# Dramco_UNO.net
KiCad netlist of a schematic drawn in EAGLE
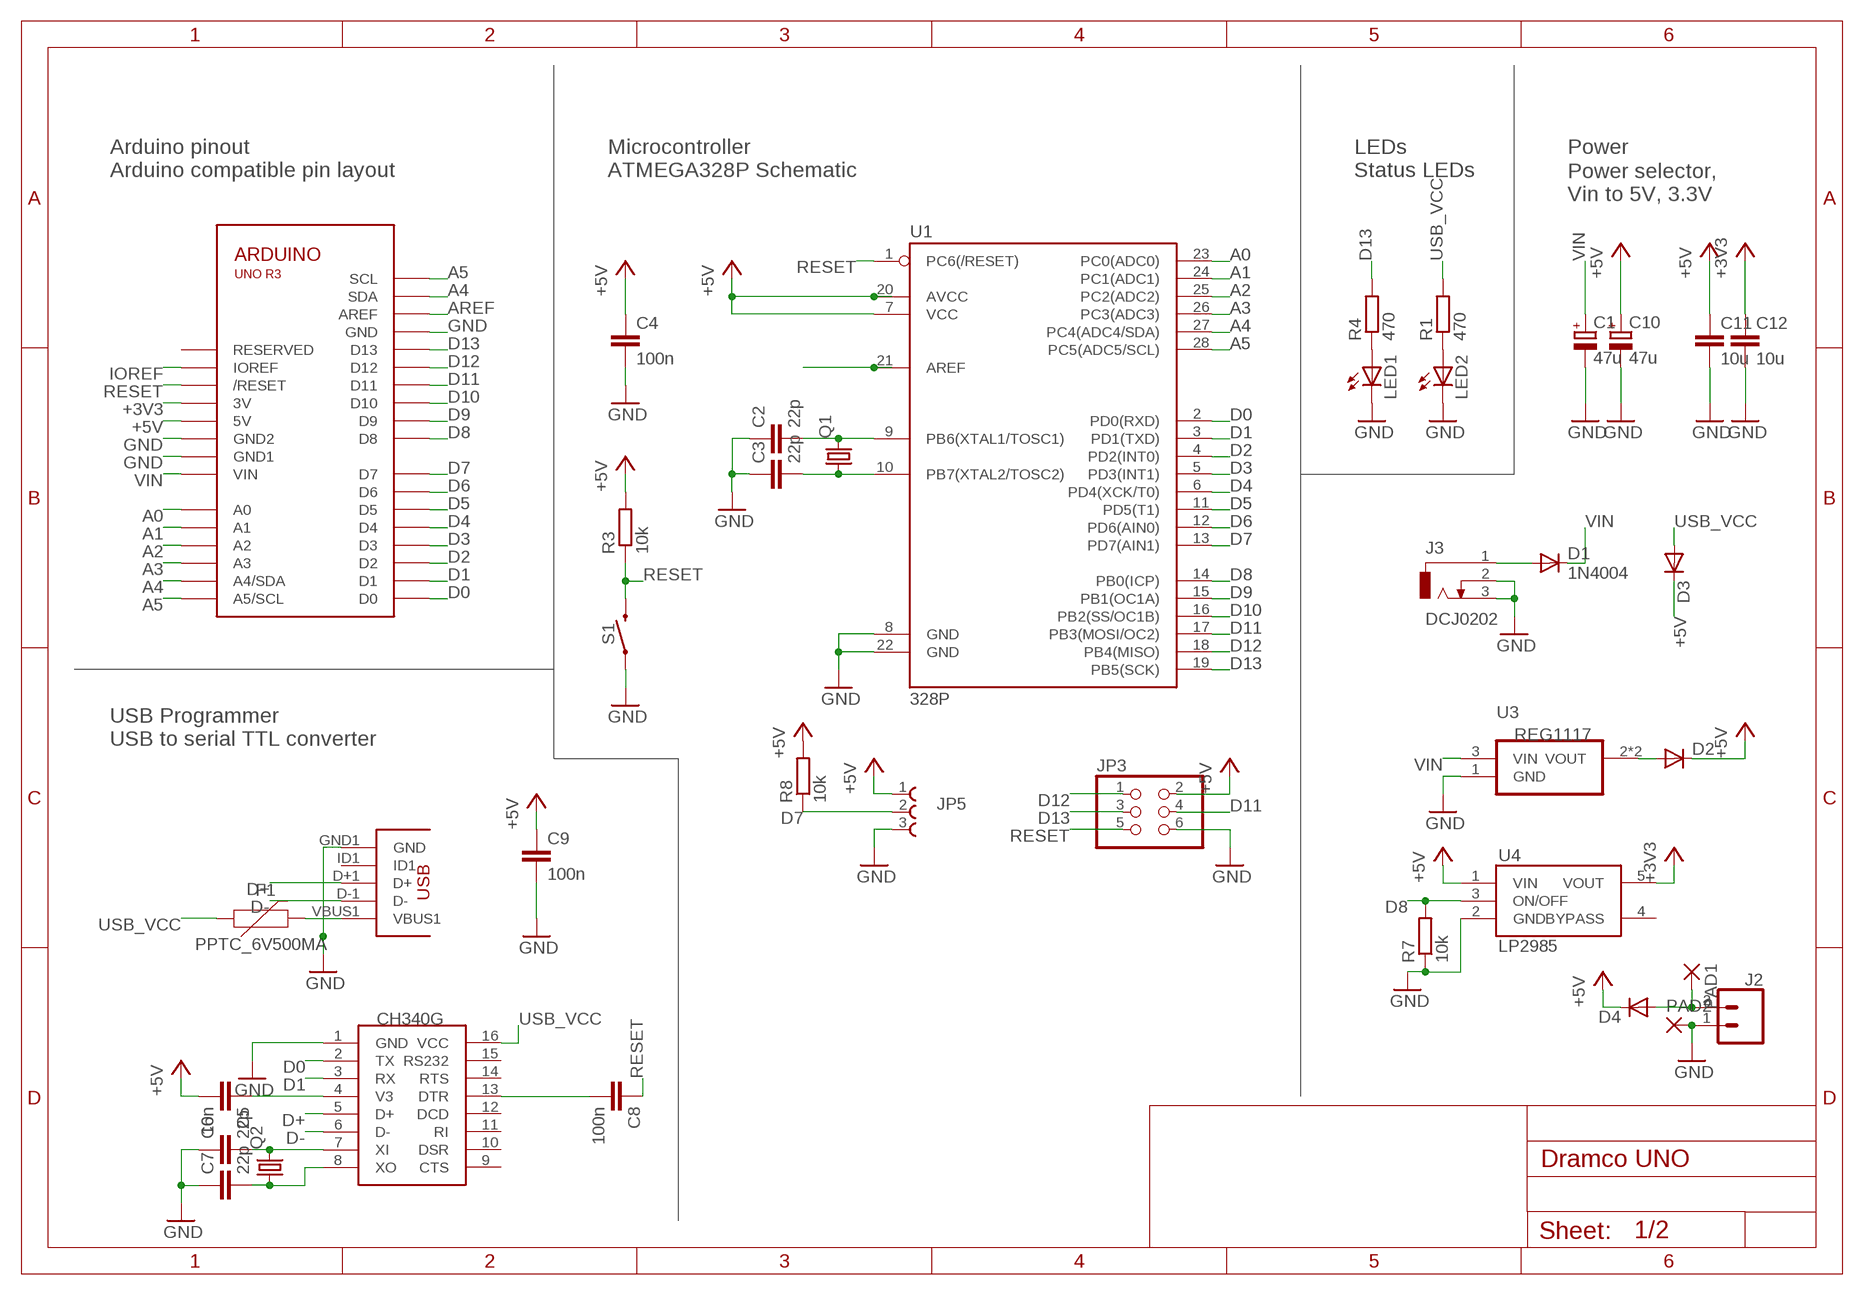
[diagram p0: schematic, sheet 1]
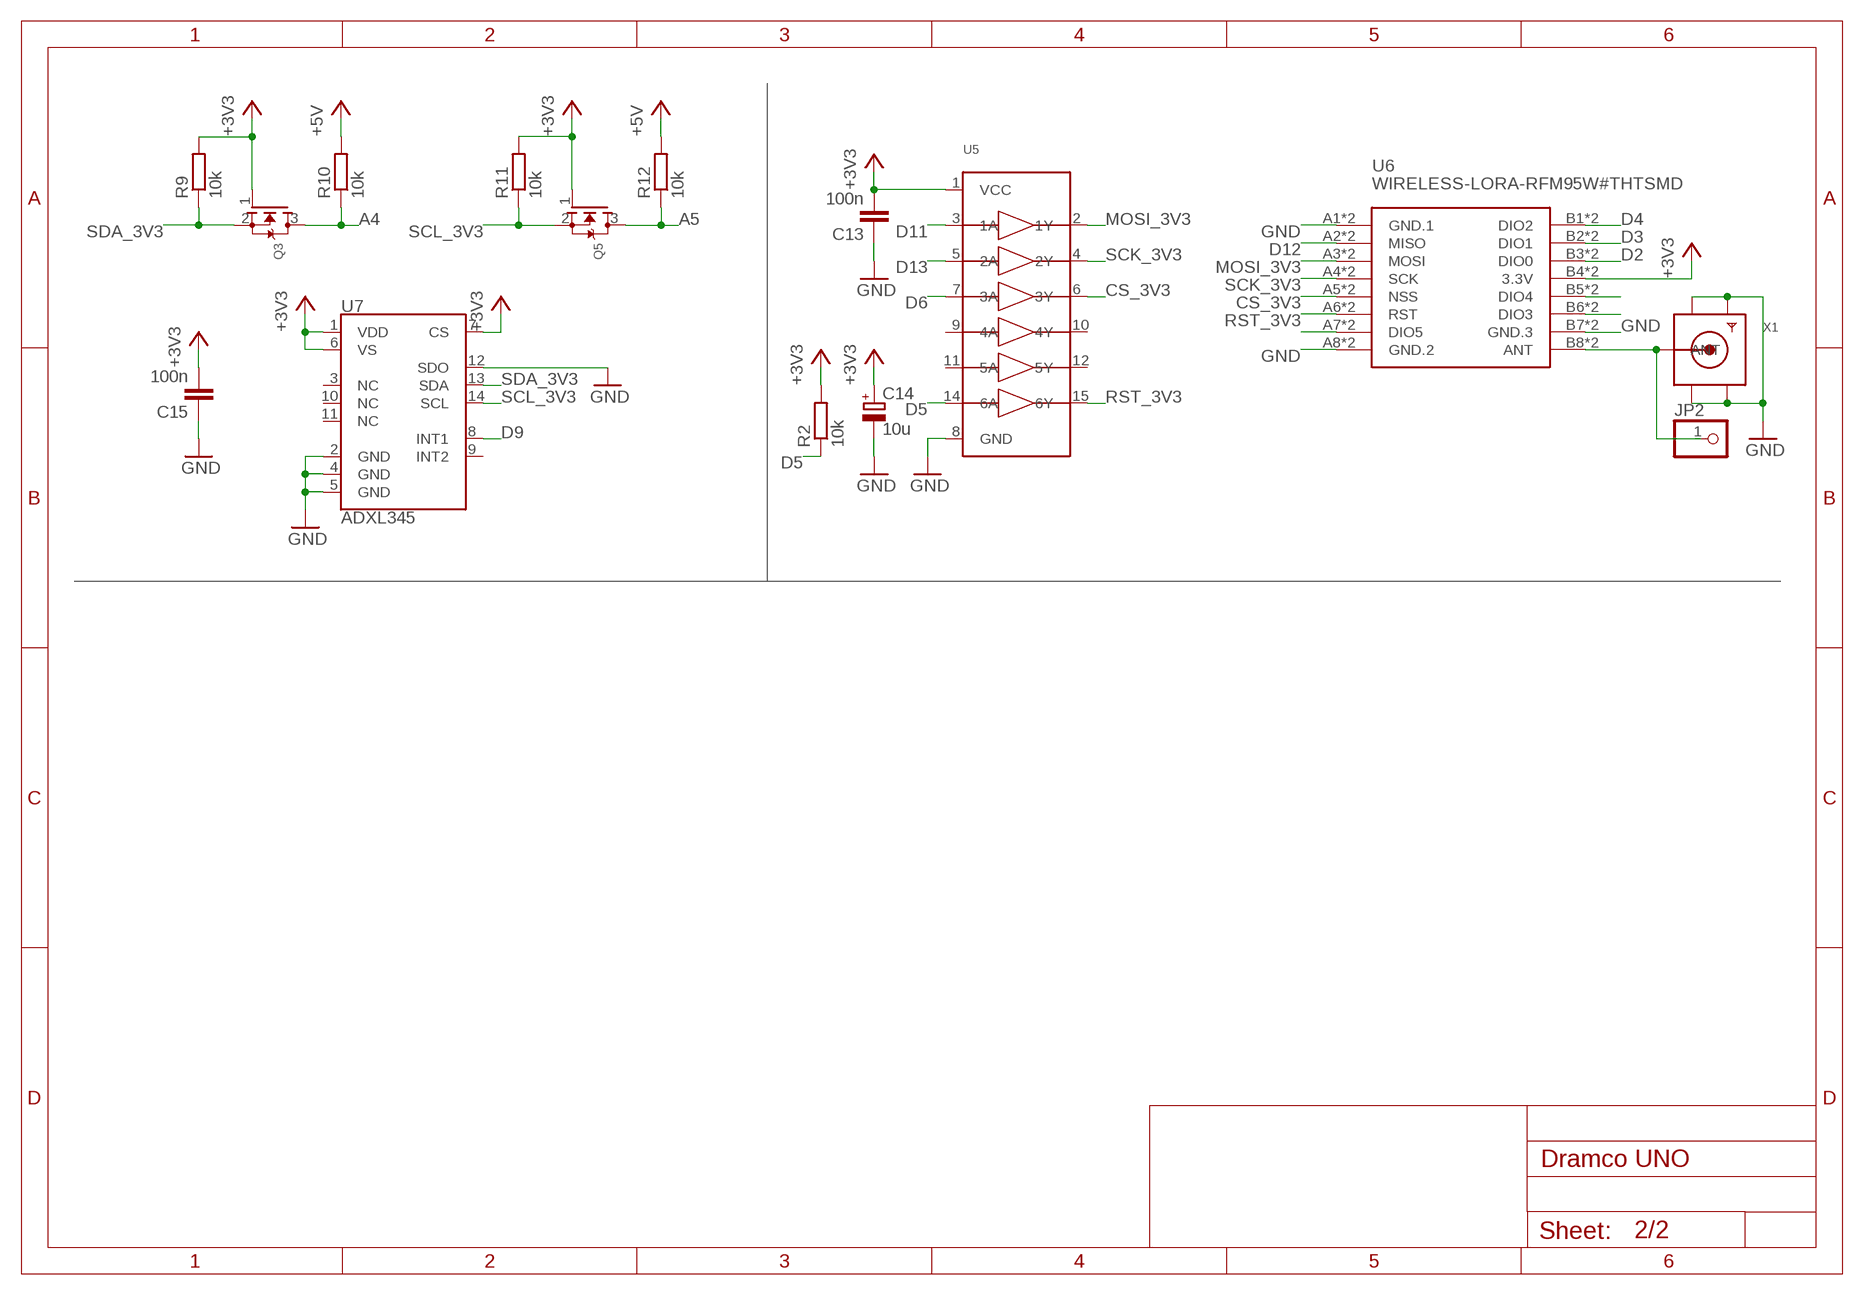
[diagram p1: schematic, sheet 2]

(export (version "E")
  (design (tool "Eeschema 10.0.6"))
  (components
    (comp (ref "C13")
      (value "100n")
      (footprint "eagle-import:C0603")
      (libsource (lib "eagle-import") (part "C-EUC0603"))
    )
    (comp (ref "C14")
      (value "10u")
      (footprint "eagle-import:E2-4")
      (libsource (lib "eagle-import") (part "CPOL-EUE2-4"))
    )
    (comp (ref "C15")
      (value "100n")
      (footprint "eagle-import:C0603")
      (libsource (lib "eagle-import") (part "C-EUC0603"))
    )
    (comp (ref "JP2")
      (value "PINHD-1X1")
      (footprint "eagle-import:1X01")
      (libsource (lib "eagle-import") (part "PINHD-1X1"))
    )
    (comp (ref "Q3")
      (value "MOSFET-NREFLOW")
      (footprint "eagle-import:SOT23")
      (libsource (lib "eagle-import") (part "MOSFET-NREFLOW"))
    )
    (comp (ref "Q5")
      (value "MOSFET-NREFLOW")
      (footprint "eagle-import:SOT23")
      (libsource (lib "eagle-import") (part "MOSFET-NREFLOW"))
    )
    (comp (ref "R2")
      (value "10k")
      (footprint "eagle-import:R0603")
      (libsource (lib "eagle-import") (part "R-EU_R0603"))
    )
    (comp (ref "R9")
      (value "10k")
      (footprint "eagle-import:R0603")
      (libsource (lib "eagle-import") (part "R-EU_R0603"))
    )
    (comp (ref "R10")
      (value "10k")
      (footprint "eagle-import:R0603")
      (libsource (lib "eagle-import") (part "R-EU_R0603"))
    )
    (comp (ref "R11")
      (value "10k")
      (footprint "eagle-import:R0603")
      (libsource (lib "eagle-import") (part "R-EU_R0603"))
    )
    (comp (ref "R12")
      (value "10k")
      (footprint "eagle-import:R0603")
      (libsource (lib "eagle-import") (part "R-EU_R0603"))
    )
    (comp (ref "U5")
      (value "74HC4050DTSSOP")
      (footprint "eagle-import:TSSOP16")
      (libsource (lib "eagle-import") (part "74HC4050DTSSOP"))
    )
    (comp (ref "U6")
      (value "WIRELESS-LORA-RFM95W#THTSMD")
      (footprint "eagle-import:WIRELESS-LORA-RFM95W#THTSMD")
      (libsource (lib "eagle-import") (part "WIRELESS-LORA-RFM95W#THTSMD"))
    )
    (comp (ref "U7")
      (value "ADXL345")
      (footprint "eagle-import:LGA-14")
      (libsource (lib "eagle-import") (part "ADXL345"))
    )
    (comp (ref "X1")
      (value "SMACONNECTOR_EDGE_UFL")
      (footprint "eagle-import:SMA_EDGELAUNCH_UFL")
      (libsource (lib "eagle-import") (part "SMACONNECTOR_EDGE_UFL"))
    )
    (comp (ref "C1")
      (value "47u")
      (footprint "eagle-import:E2,5-6")
      (libsource (lib "eagle-import") (part "CPOL-EUE2.5-6"))
    )
    (comp (ref "C2")
      (value "22p")
      (footprint "eagle-import:C025-024X044")
      (libsource (lib "eagle-import") (part "resistor_C-EU025-024X044"))
    )
    (comp (ref "C3")
      (value "22p")
      (footprint "eagle-import:C025-024X044")
      (libsource (lib "eagle-import") (part "resistor_C-EU025-024X044"))
    )
    (comp (ref "C4")
      (value "100n")
      (footprint "eagle-import:C025-024X044")
      (libsource (lib "eagle-import") (part "resistor_C-EU025-024X044"))
    )
    (comp (ref "C5")
      (value "10n")
      (footprint "eagle-import:C0603")
      (libsource (lib "eagle-import") (part "resistor_C-EUC0603"))
    )
    (comp (ref "C6")
      (value "22p")
      (footprint "eagle-import:C0603")
      (libsource (lib "eagle-import") (part "resistor_C-EUC0603"))
    )
    (comp (ref "C7")
      (value "22p")
      (footprint "eagle-import:C0603")
      (libsource (lib "eagle-import") (part "resistor_C-EUC0603"))
    )
    (comp (ref "C8")
      (value "100n")
      (footprint "eagle-import:C0603")
      (libsource (lib "eagle-import") (part "resistor_C-EUC0603"))
    )
    (comp (ref "C9")
      (value "100n")
      (footprint "eagle-import:C0603")
      (libsource (lib "eagle-import") (part "resistor_C-EUC0603"))
    )
    (comp (ref "C10")
      (value "47u")
      (footprint "eagle-import:E2,5-6")
      (libsource (lib "eagle-import") (part "CPOL-EUE2.5-6"))
    )
    (comp (ref "C11")
      (value "10u")
      (footprint "eagle-import:C0603")
      (libsource (lib "eagle-import") (part "C-EUC0603"))
    )
    (comp (ref "C12")
      (value "10u")
      (footprint "eagle-import:C0603")
      (libsource (lib "eagle-import") (part "C-EUC0603"))
    )
    (comp (ref "D1")
      (value "1N4004")
      (footprint "eagle-import:DO41-10")
      (libsource (lib "eagle-import") (part "1N4004"))
    )
    (comp (ref "D2")
      (value "DIODE-SOD123")
      (footprint "eagle-import:SOD123")
      (libsource (lib "eagle-import") (part "DIODE-SOD123"))
    )
    (comp (ref "D3")
      (value "DIODE-SOD123")
      (footprint "eagle-import:SOD123")
      (libsource (lib "eagle-import") (part "DIODE-SOD123"))
    )
    (comp (ref "D4")
      (value "DIODE-SOD123")
      (footprint "eagle-import:SOD123")
      (libsource (lib "eagle-import") (part "DIODE-SOD123"))
    )
    (comp (ref "F1")
      (value "PPTC_6V500MA")
      (footprint "eagle-import:0805")
      (libsource (lib "eagle-import") (part "PPTC_6V500MA"))
    )
    (comp (ref "J1")
      (value "USB-AB")
      (footprint "eagle-import:USB-AB-MICRO-SMD_V02_BOSS")
      (libsource (lib "eagle-import") (part "USB-AB"))
    )
    (comp (ref "J2")
      (value "CONN_02JST-PTH-2")
      (footprint "eagle-import:JST-2-PTH")
      (libsource (lib "eagle-import") (part "CONN_02JST-PTH-2"))
    )
    (comp (ref "J3")
      (value "DCJ0202")
      (footprint "eagle-import:DCJ0202")
      (libsource (lib "eagle-import") (part "DCJ0202"))
    )
    (comp (ref "JP1")
      (value "ARDUINOR3-DIMENSION")
      (footprint "eagle-import:ARDUINOR3")
      (libsource (lib "eagle-import") (part "ARDUINOR3-DIMENSION"))
    )
    (comp (ref "JP3")
      (value "PINHD-2X3")
      (footprint "eagle-import:2X03")
      (libsource (lib "eagle-import") (part "PINHD-2X3"))
    )
    (comp (ref "JP5")
      (value "691210910003")
      (footprint "eagle-import:691210910003")
      (libsource (lib "eagle-import") (part "691210910003"))
    )
    (comp (ref "LED1")
      (value "LED5MM")
      (footprint "eagle-import:LED5MM")
      (libsource (lib "eagle-import") (part "LED5MM"))
    )
    (comp (ref "LED2")
      (value "LED5MM")
      (footprint "eagle-import:LED5MM")
      (libsource (lib "eagle-import") (part "LED5MM"))
    )
    (comp (ref "PAD1")
      (value "SMD2")
      (footprint "eagle-import:SMD1,27-2,54")
      (libsource (lib "eagle-import") (part "SMD2"))
    )
    (comp (ref "PAD2")
      (value "SMD2")
      (footprint "eagle-import:SMD1,27-2,54")
      (libsource (lib "eagle-import") (part "SMD2"))
    )
    (comp (ref "Q1")
      (value "CRYSTALHC49S")
      (footprint "eagle-import:HC49_S")
      (libsource (lib "eagle-import") (part "CRYSTALHC49S"))
    )
    (comp (ref "Q2")
      (value "CRYSTALHC49S")
      (footprint "eagle-import:HC49_S")
      (libsource (lib "eagle-import") (part "CRYSTALHC49S"))
    )
    (comp (ref "R1")
      (value "470")
      (footprint "eagle-import:0204_7")
      (libsource (lib "eagle-import") (part "resistor_R-EU_0204/7"))
    )
    (comp (ref "R3")
      (value "10k")
      (footprint "eagle-import:0204_7")
      (libsource (lib "eagle-import") (part "resistor_R-EU_0204/7"))
    )
    (comp (ref "R4")
      (value "470")
      (footprint "eagle-import:0204_7")
      (libsource (lib "eagle-import") (part "resistor_R-EU_0204/7"))
    )
    (comp (ref "R7")
      (value "10k")
      (footprint "eagle-import:R0603")
      (libsource (lib "eagle-import") (part "R-EU_R0603"))
    )
    (comp (ref "R8")
      (value "10k")
      (footprint "eagle-import:0204_7")
      (libsource (lib "eagle-import") (part "resistor_R-EU_0204/7"))
    )
    (comp (ref "S1")
      (value "MOMENTARY-SWITCH-SPST-PTH-6.0MM")
      (footprint "eagle-import:TACTILE_SWITCH_PTH_6.0MM")
      (libsource (lib "eagle-import") (part "MOMENTARY-SWITCH-SPST-PTH-6.0MM"))
    )
    (comp (ref "U1")
      (value "328P")
      (footprint "eagle-import:DIP28")
      (libsource (lib "eagle-import") (part "ATMEGA328P_PDIP"))
    )
    (comp (ref "U2")
      (value "CH340G")
      (footprint "eagle-import:SOIC16")
      (libsource (lib "eagle-import") (part "CH340G"))
    )
    (comp (ref "U3")
      (value "REG1117")
      (footprint "eagle-import:SOT223")
      (libsource (lib "eagle-import") (part "REG1117"))
    )
    (comp (ref "U4")
      (value "LP2985AIM5-3.3")
      (footprint "eagle-import:SOT25")
      (libsource (lib "eagle-import") (part "LP2985AIM5-3.3"))
    )
  )
  (nets
    (net (code "1") (name "+3V3") (class "Default")
      (node (ref "C12") (pin "1") (pinfunction "1_1") (pintype "passive"))
      (node (ref "C13") (pin "2") (pinfunction "2_2") (pintype "passive"))
      (node (ref "C14") (pin "+") (pinfunction "+_+") (pintype "passive"))
      (node (ref "C15") (pin "2") (pinfunction "2_2") (pintype "passive"))
      (node (ref "JP1") (pin "3V") (pinfunction "3V_3V") (pintype "power_in"))
      (node (ref "Q3") (pin "1") (pinfunction "G_1") (pintype "bidirectional"))
      (node (ref "Q5") (pin "1") (pinfunction "G_1") (pintype "bidirectional"))
      (node (ref "R11") (pin "2") (pinfunction "2_2") (pintype "passive"))
      (node (ref "R2") (pin "2") (pinfunction "2_2") (pintype "passive"))
      (node (ref "R9") (pin "2") (pinfunction "2_2") (pintype "passive"))
      (node (ref "U4") (pin "5") (pinfunction "VOUT_5") (pintype "power_in"))
      (node (ref "U5") (pin "1") (pinfunction "VCC_1") (pintype "bidirectional"))
      (node (ref "U6") (pin "B12") (pinfunction "3.3V_B12") (pintype "power_in"))
      (node (ref "U6") (pin "B4") (pinfunction "3.3V_B4") (pintype "power_in"))
      (node (ref "U7") (pin "1") (pinfunction "VDD_1") (pintype "bidirectional"))
      (node (ref "U7") (pin "6") (pinfunction "VS_6") (pintype "bidirectional"))
      (node (ref "U7") (pin "7") (pinfunction "CS_7") (pintype "bidirectional"))
    )
    (net (code "2") (name "+5V") (class "Default")
      (node (ref "C10") (pin "+") (pinfunction "+_+") (pintype "passive"))
      (node (ref "C11") (pin "1") (pinfunction "1_1") (pintype "passive"))
      (node (ref "C4") (pin "1") (pinfunction "1_1") (pintype "passive"))
      (node (ref "C5") (pin "2") (pinfunction "2_2") (pintype "passive"))
      (node (ref "C9") (pin "1") (pinfunction "1_1") (pintype "passive"))
      (node (ref "D2") (pin "C") (pinfunction "C_C") (pintype "passive"))
      (node (ref "D3") (pin "C") (pinfunction "C_C") (pintype "passive"))
      (node (ref "D4") (pin "C") (pinfunction "C_C") (pintype "passive"))
      (node (ref "JP1") (pin "5V") (pinfunction "5V_5V") (pintype "power_in"))
      (node (ref "JP3") (pin "2") (pinfunction "2_2") (pintype "passive"))
      (node (ref "JP5") (pin "1") (pinfunction "1_1") (pintype "passive"))
      (node (ref "R10") (pin "2") (pinfunction "2_2") (pintype "passive"))
      (node (ref "R12") (pin "2") (pinfunction "2_2") (pintype "passive"))
      (node (ref "R3") (pin "2") (pinfunction "2_2") (pintype "passive"))
      (node (ref "R8") (pin "2") (pinfunction "2_2") (pintype "passive"))
      (node (ref "U1") (pin "20") (pinfunction "AVCC_20") (pintype "bidirectional"))
      (node (ref "U1") (pin "7") (pinfunction "VCC_7") (pintype "bidirectional"))
      (node (ref "U4") (pin "1") (pinfunction "VIN_1") (pintype "power_in"))
    )
    (net (code "3") (name "A0") (class "Default")
      (node (ref "JP1") (pin "A0") (pinfunction "A0_A0") (pintype "bidirectional"))
      (node (ref "U1") (pin "23") (pinfunction "PC0(ADC0)_23") (pintype "bidirectional"))
    )
    (net (code "4") (name "A1") (class "Default")
      (node (ref "JP1") (pin "A1") (pinfunction "A1_A1") (pintype "bidirectional"))
      (node (ref "U1") (pin "24") (pinfunction "PC1(ADC1)_24") (pintype "bidirectional"))
    )
    (net (code "5") (name "A2") (class "Default")
      (node (ref "JP1") (pin "A2") (pinfunction "A2_A2") (pintype "bidirectional"))
      (node (ref "U1") (pin "25") (pinfunction "PC2(ADC2)_25") (pintype "bidirectional"))
    )
    (net (code "6") (name "A3") (class "Default")
      (node (ref "JP1") (pin "A3") (pinfunction "A3_A3") (pintype "bidirectional"))
      (node (ref "U1") (pin "26") (pinfunction "PC3(ADC3)_26") (pintype "bidirectional"))
    )
    (net (code "7") (name "A4") (class "Default")
      (node (ref "JP1") (pin "A4") (pinfunction "A4/SDA_A4") (pintype "bidirectional"))
      (node (ref "JP1") (pin "SDA") (pinfunction "SDA_SDA") (pintype "bidirectional"))
      (node (ref "Q3") (pin "3") (pinfunction "D_3") (pintype "bidirectional"))
      (node (ref "R10") (pin "1") (pinfunction "1_1") (pintype "passive"))
      (node (ref "U1") (pin "27") (pinfunction "PC4(ADC4/SDA)_27") (pintype "bidirectional"))
    )
    (net (code "8") (name "A5") (class "Default")
      (node (ref "JP1") (pin "A5") (pinfunction "A5/SCL_A5") (pintype "bidirectional"))
      (node (ref "JP1") (pin "SCL") (pinfunction "SCL_SCL") (pintype "bidirectional"))
      (node (ref "Q5") (pin "3") (pinfunction "D_3") (pintype "bidirectional"))
      (node (ref "R12") (pin "1") (pinfunction "1_1") (pintype "passive"))
      (node (ref "U1") (pin "28") (pinfunction "PC5(ADC5/SCL)_28") (pintype "bidirectional"))
    )
    (net (code "9") (name "AREF") (class "Default")
      (node (ref "JP1") (pin "AREF") (pinfunction "AREF_AREF") (pintype "bidirectional"))
      (node (ref "U1") (pin "21") (pinfunction "AREF_21") (pintype "bidirectional"))
    )
    (net (code "10") (name "BYPASS") (class "Default")
      (node (ref "U4") (pin "4") (pinfunction "BYPASS_4") (pintype "power_in"))
    )
    (net (code "11") (name "CS_3V3") (class "Default")
      (node (ref "U5") (pin "6") (pinfunction "3Y_6") (pintype "bidirectional"))
      (node (ref "U6") (pin "A13") (pinfunction "NSS_A13") (pintype "bidirectional"))
      (node (ref "U6") (pin "A5") (pinfunction "NSS_A5") (pintype "bidirectional"))
    )
    (net (code "12") (name "D+") (class "Default")
      (node (ref "J1") (pin "D+1") (pinfunction "D+_D+1") (pintype "bidirectional"))
      (node (ref "U2") (pin "5") (pinfunction "D+_5") (pintype "bidirectional"))
    )
    (net (code "13") (name "D-") (class "Default")
      (node (ref "J1") (pin "D-1") (pinfunction "D-_D-1") (pintype "bidirectional"))
      (node (ref "U2") (pin "6") (pinfunction "D-_6") (pintype "bidirectional"))
    )
    (net (code "14") (name "D0") (class "Default")
      (node (ref "JP1") (pin "D0") (pinfunction "D0_D0") (pintype "bidirectional"))
      (node (ref "U1") (pin "2") (pinfunction "PD0(RXD)_2") (pintype "bidirectional"))
      (node (ref "U2") (pin "2") (pinfunction "TX_2") (pintype "bidirectional"))
    )
    (net (code "15") (name "D1") (class "Default")
      (node (ref "JP1") (pin "D1") (pinfunction "D1_D1") (pintype "bidirectional"))
      (node (ref "U1") (pin "3") (pinfunction "PD1(TXD)_3") (pintype "bidirectional"))
      (node (ref "U2") (pin "3") (pinfunction "RX_3") (pintype "bidirectional"))
    )
    (net (code "16") (name "D2") (class "Default")
      (node (ref "JP1") (pin "D2") (pinfunction "D2_D2") (pintype "bidirectional"))
      (node (ref "U1") (pin "4") (pinfunction "PD2(INT0)_4") (pintype "bidirectional"))
      (node (ref "U6") (pin "B11") (pinfunction "DIO0_B11") (pintype "bidirectional"))
      (node (ref "U6") (pin "B3") (pinfunction "DIO0_B3") (pintype "bidirectional"))
    )
    (net (code "17") (name "D3") (class "Default")
      (node (ref "JP1") (pin "D3") (pinfunction "D3_D3") (pintype "bidirectional"))
      (node (ref "U1") (pin "5") (pinfunction "PD3(INT1)_5") (pintype "bidirectional"))
      (node (ref "U6") (pin "B10") (pinfunction "DIO1_B10") (pintype "bidirectional"))
      (node (ref "U6") (pin "B2") (pinfunction "DIO1_B2") (pintype "bidirectional"))
    )
    (net (code "18") (name "D4") (class "Default")
      (node (ref "JP1") (pin "D4") (pinfunction "D4_D4") (pintype "bidirectional"))
      (node (ref "U1") (pin "6") (pinfunction "PD4(XCK/T0)_6") (pintype "bidirectional"))
      (node (ref "U6") (pin "B1") (pinfunction "DIO2_B1") (pintype "bidirectional"))
      (node (ref "U6") (pin "B9") (pinfunction "DIO2_B9") (pintype "bidirectional"))
    )
    (net (code "19") (name "D5") (class "Default")
      (node (ref "JP1") (pin "D5") (pinfunction "D5_D5") (pintype "bidirectional"))
      (node (ref "R2") (pin "1") (pinfunction "1_1") (pintype "passive"))
      (node (ref "U1") (pin "11") (pinfunction "PD5(T1)_11") (pintype "bidirectional"))
      (node (ref "U5") (pin "14") (pinfunction "6A_14") (pintype "bidirectional"))
    )
    (net (code "20") (name "D6") (class "Default")
      (node (ref "JP1") (pin "D6") (pinfunction "D6_D6") (pintype "bidirectional"))
      (node (ref "U1") (pin "12") (pinfunction "PD6(AIN0)_12") (pintype "bidirectional"))
      (node (ref "U5") (pin "7") (pinfunction "3A_7") (pintype "bidirectional"))
    )
    (net (code "21") (name "D7") (class "Default")
      (node (ref "JP1") (pin "D7") (pinfunction "D7_D7") (pintype "bidirectional"))
      (node (ref "JP5") (pin "2") (pinfunction "2_2") (pintype "passive"))
      (node (ref "R8") (pin "1") (pinfunction "1_1") (pintype "passive"))
      (node (ref "U1") (pin "13") (pinfunction "PD7(AIN1)_13") (pintype "bidirectional"))
    )
    (net (code "22") (name "D8") (class "Default")
      (node (ref "JP1") (pin "D8") (pinfunction "D8_D8") (pintype "bidirectional"))
      (node (ref "R7") (pin "2") (pinfunction "2_2") (pintype "passive"))
      (node (ref "U1") (pin "14") (pinfunction "PB0(ICP)_14") (pintype "bidirectional"))
      (node (ref "U4") (pin "3") (pinfunction "ON/OFF_3") (pintype "input"))
    )
    (net (code "23") (name "D9") (class "Default")
      (node (ref "JP1") (pin "D9") (pinfunction "D9_D9") (pintype "bidirectional"))
      (node (ref "U1") (pin "15") (pinfunction "PB1(OC1A)_15") (pintype "bidirectional"))
      (node (ref "U7") (pin "8") (pinfunction "INT1_8") (pintype "bidirectional"))
    )
    (net (code "24") (name "D10") (class "Default")
      (node (ref "JP1") (pin "D10") (pinfunction "D10_D10") (pintype "bidirectional"))
      (node (ref "U1") (pin "16") (pinfunction "PB2(SS/OC1B)_16") (pintype "bidirectional"))
    )
    (net (code "25") (name "D11") (class "Default")
      (node (ref "JP1") (pin "D11") (pinfunction "D11_D11") (pintype "bidirectional"))
      (node (ref "JP3") (pin "4") (pinfunction "4_4") (pintype "passive"))
      (node (ref "U1") (pin "17") (pinfunction "PB3(MOSI/OC2)_17") (pintype "bidirectional"))
      (node (ref "U5") (pin "3") (pinfunction "1A_3") (pintype "bidirectional"))
    )
    (net (code "26") (name "D12") (class "Default")
      (node (ref "JP1") (pin "D12") (pinfunction "D12_D12") (pintype "bidirectional"))
      (node (ref "JP3") (pin "1") (pinfunction "1_1") (pintype "passive"))
      (node (ref "U1") (pin "18") (pinfunction "PB4(MISO)_18") (pintype "bidirectional"))
      (node (ref "U6") (pin "A10") (pinfunction "MISO_A10") (pintype "bidirectional"))
      (node (ref "U6") (pin "A2") (pinfunction "MISO_A2") (pintype "bidirectional"))
    )
    (net (code "27") (name "D13") (class "Default")
      (node (ref "JP1") (pin "D13") (pinfunction "D13_D13") (pintype "bidirectional"))
      (node (ref "JP3") (pin "3") (pinfunction "3_3") (pintype "passive"))
      (node (ref "R4") (pin "2") (pinfunction "2_2") (pintype "passive"))
      (node (ref "U1") (pin "19") (pinfunction "PB5(SCK)_19") (pintype "bidirectional"))
      (node (ref "U5") (pin "5") (pinfunction "2A_5") (pintype "bidirectional"))
    )
    (net (code "28") (name "GND") (class "Default")
      (node (ref "C1") (pin "-") (pinfunction "-_-") (pintype "passive"))
      (node (ref "C10") (pin "-") (pinfunction "-_-") (pintype "passive"))
      (node (ref "C11") (pin "2") (pinfunction "2_2") (pintype "passive"))
      (node (ref "C12") (pin "2") (pinfunction "2_2") (pintype "passive"))
      (node (ref "C13") (pin "1") (pinfunction "1_1") (pintype "passive"))
      (node (ref "C14") (pin "-") (pinfunction "-_-") (pintype "passive"))
      (node (ref "C15") (pin "1") (pinfunction "1_1") (pintype "passive"))
      (node (ref "C2") (pin "1") (pinfunction "1_1") (pintype "passive"))
      (node (ref "C3") (pin "1") (pinfunction "1_1") (pintype "passive"))
      (node (ref "C4") (pin "2") (pinfunction "2_2") (pintype "passive"))
      (node (ref "C6") (pin "1") (pinfunction "1_1") (pintype "passive"))
      (node (ref "C7") (pin "1") (pinfunction "1_1") (pintype "passive"))
      (node (ref "C9") (pin "2") (pinfunction "2_2") (pintype "passive"))
      (node (ref "J1") (pin "GND1") (pinfunction "GND_GND1") (pintype "bidirectional"))
      (node (ref "J2") (pin "1") (pinfunction "1_1") (pintype "passive"))
      (node (ref "J3") (pin "2") (pinfunction "2_2") (pintype "passive"))
      (node (ref "J3") (pin "3") (pinfunction "3_3") (pintype "passive"))
      (node (ref "JP1") (pin "GND") (pinfunction "GND_GND") (pintype "power_in"))
      (node (ref "JP1") (pin "GND1") (pinfunction "GND1_GND1") (pintype "power_in"))
      (node (ref "JP1") (pin "GND2") (pinfunction "GND2_GND2") (pintype "power_in"))
      (node (ref "JP3") (pin "6") (pinfunction "6_6") (pintype "passive"))
      (node (ref "JP5") (pin "3") (pinfunction "3_3") (pintype "passive"))
      (node (ref "LED1") (pin "K") (pinfunction "C_K") (pintype "passive"))
      (node (ref "LED2") (pin "K") (pinfunction "C_K") (pintype "passive"))
      (node (ref "PAD2") (pin "1") (pinfunction "P_1") (pintype "passive"))
      (node (ref "R7") (pin "1") (pinfunction "1_1") (pintype "passive"))
      (node (ref "S1") (pin "1") (pinfunction "1_1") (pintype "passive"))
      (node (ref "U1") (pin "22") (pinfunction "GND_22") (pintype "bidirectional"))
      (node (ref "U1") (pin "8") (pinfunction "GND_8") (pintype "bidirectional"))
      (node (ref "U2") (pin "1") (pinfunction "GND_1") (pintype "bidirectional"))
      (node (ref "U3") (pin "1") (pinfunction "GND_1") (pintype "power_in"))
      (node (ref "U4") (pin "2") (pinfunction "GND_2") (pintype "power_in"))
      (node (ref "U5") (pin "8") (pinfunction "GND_8") (pintype "bidirectional"))
      (node (ref "U6") (pin "A1") (pinfunction "GND.1_A1") (pintype "power_in"))
      (node (ref "U6") (pin "A16") (pinfunction "GND.2_A16") (pintype "power_in"))
      (node (ref "U6") (pin "A8") (pinfunction "GND.2_A8") (pintype "power_in"))
      (node (ref "U6") (pin "A9") (pinfunction "GND.1_A9") (pintype "power_in"))
      (node (ref "U6") (pin "B15") (pinfunction "GND.3_B15") (pintype "power_in"))
      (node (ref "U6") (pin "B7") (pinfunction "GND.3_B7") (pintype "power_in"))
      (node (ref "U7") (pin "12") (pinfunction "SDO_12") (pintype "bidirectional"))
      (node (ref "U7") (pin "2") (pinfunction "GND_2") (pintype "bidirectional"))
      (node (ref "U7") (pin "4") (pinfunction "GND_4") (pintype "bidirectional"))
      (node (ref "U7") (pin "5") (pinfunction "GND_5") (pintype "bidirectional"))
      (node (ref "X1") (pin "GND@1") (pinfunction "GND1_GND@1") (pintype "power_in"))
      (node (ref "X1") (pin "GND@2") (pinfunction "GND2_GND@2") (pintype "power_in"))
      (node (ref "X1") (pin "GND@3") (pinfunction "GND3_GND@3") (pintype "power_in"))
      (node (ref "X1") (pin "GND@4") (pinfunction "GND4_GND@4") (pintype "power_in"))
    )
    (net (code "29") (name "IOREF") (class "Default")
      (node (ref "JP1") (pin "IOREF") (pinfunction "IOREF_IOREF") (pintype "output"))
    )
    (net (code "30") (name "MOSI_3V3") (class "Default")
      (node (ref "U5") (pin "2") (pinfunction "1Y_2") (pintype "bidirectional"))
      (node (ref "U6") (pin "A11") (pinfunction "MOSI_A11") (pintype "bidirectional"))
      (node (ref "U6") (pin "A3") (pinfunction "MOSI_A3") (pintype "bidirectional"))
    )
    (net (code "31") (name "Net-(D1-PadA)") (class "Default")
      (node (ref "D1") (pin "A") (pinfunction "A_A") (pintype "passive"))
      (node (ref "J3") (pin "1") (pinfunction "1_1") (pintype "passive"))
    )
    (net (code "32") (name "Net-(D2-PadA)") (class "Default")
      (node (ref "D2") (pin "A") (pinfunction "A_A") (pintype "passive"))
      (node (ref "U3") (pin "2") (pinfunction "VOUT_2") (pintype "output"))
      (node (ref "U3") (pin "4") (pinfunction "VOUT_4") (pintype "output"))
    )
    (net (code "33") (name "Net-(F1-Pad2)") (class "Default")
      (node (ref "F1") (pin "2") (pinfunction "2_2") (pintype "bidirectional"))
      (node (ref "J1") (pin "VBUS1") (pinfunction "VBUS1_VBUS1") (pintype "bidirectional"))
    )
    (net (code "34") (name "Net-(LED1-PadA)") (class "Default")
      (node (ref "LED1") (pin "A") (pinfunction "A_A") (pintype "passive"))
      (node (ref "R4") (pin "1") (pinfunction "1_1") (pintype "passive"))
    )
    (net (code "35") (name "Net-(LED2-PadA)") (class "Default")
      (node (ref "LED2") (pin "A") (pinfunction "A_A") (pintype "passive"))
      (node (ref "R1") (pin "1") (pinfunction "1_1") (pintype "passive"))
    )
    (net (code "36") (name "Net-(PAD1-P)") (class "Default")
      (node (ref "D4") (pin "A") (pinfunction "A_A") (pintype "passive"))
      (node (ref "J2") (pin "2") (pinfunction "2_2") (pintype "passive"))
      (node (ref "PAD1") (pin "1") (pinfunction "P_1") (pintype "passive"))
    )
    (net (code "37") (name "Net-(U1-PB6(XTAL1{slash}TOSC1))") (class "Default")
      (node (ref "C2") (pin "2") (pinfunction "2_2") (pintype "passive"))
      (node (ref "Q1") (pin "2") (pinfunction "2_2") (pintype "passive"))
      (node (ref "U1") (pin "9") (pinfunction "PB6(XTAL1/TOSC1)_9") (pintype "bidirectional"))
    )
    (net (code "38") (name "Net-(U1-PB7(XTAL2{slash}TOSC2))") (class "Default")
      (node (ref "C3") (pin "2") (pinfunction "2_2") (pintype "passive"))
      (node (ref "Q1") (pin "1") (pinfunction "1_1") (pintype "passive"))
      (node (ref "U1") (pin "10") (pinfunction "PB7(XTAL2/TOSC2)_10") (pintype "bidirectional"))
    )
    (net (code "39") (name "Net-(U2-DTR)") (class "Default")
      (node (ref "C8") (pin "2") (pinfunction "2_2") (pintype "passive"))
      (node (ref "U2") (pin "13") (pinfunction "DTR_13") (pintype "bidirectional"))
    )
    (net (code "40") (name "Net-(U2-V3)") (class "Default")
      (node (ref "C5") (pin "1") (pinfunction "1_1") (pintype "passive"))
      (node (ref "U2") (pin "4") (pinfunction "V3_4") (pintype "bidirectional"))
    )
    (net (code "41") (name "Net-(U2-XI)") (class "Default")
      (node (ref "C6") (pin "2") (pinfunction "2_2") (pintype "passive"))
      (node (ref "Q2") (pin "2") (pinfunction "2_2") (pintype "passive"))
      (node (ref "U2") (pin "7") (pinfunction "XI_7") (pintype "bidirectional"))
    )
    (net (code "42") (name "Net-(U2-XO)") (class "Default")
      (node (ref "C7") (pin "2") (pinfunction "2_2") (pintype "passive"))
      (node (ref "Q2") (pin "1") (pinfunction "1_1") (pintype "passive"))
      (node (ref "U2") (pin "8") (pinfunction "XO_8") (pintype "bidirectional"))
    )
    (net (code "43") (name "Net-(U6-DIO3-PadB14)") (class "Default")
      (node (ref "U6") (pin "B14") (pinfunction "DIO3_B14") (pintype "bidirectional"))
      (node (ref "U6") (pin "B6") (pinfunction "DIO3_B6") (pintype "bidirectional"))
    )
    (net (code "44") (name "Net-(U6-DIO4-PadB13)") (class "Default")
      (node (ref "U6") (pin "B13") (pinfunction "DIO4_B13") (pintype "bidirectional"))
      (node (ref "U6") (pin "B5") (pinfunction "DIO4_B5") (pintype "bidirectional"))
    )
    (net (code "45") (name "Net-(U6-DIO5-PadA15)") (class "Default")
      (node (ref "U6") (pin "A15") (pinfunction "DIO5_A15") (pintype "bidirectional"))
      (node (ref "U6") (pin "A7") (pinfunction "DIO5_A7") (pintype "bidirectional"))
    )
    (net (code "46") (name "Net-(X1-ANT)") (class "Default")
      (node (ref "JP2") (pin "1") (pinfunction "1_1") (pintype "passive"))
      (node (ref "U6") (pin "B16") (pinfunction "ANT_B16") (pintype "passive"))
      (node (ref "U6") (pin "B8") (pinfunction "ANT_B8") (pintype "passive"))
      (node (ref "X1") (pin "P") (pinfunction "ANT_P") (pintype "bidirectional"))
    )
    (net (code "47") (name "RESET") (class "Default")
      (node (ref "C8") (pin "1") (pinfunction "1_1") (pintype "passive"))
      (node (ref "JP1") (pin "RESET") (pinfunction "/RESET_RESET") (pintype "bidirectional"))
      (node (ref "JP3") (pin "5") (pinfunction "5_5") (pintype "passive"))
      (node (ref "R3") (pin "1") (pinfunction "1_1") (pintype "passive"))
      (node (ref "S1") (pin "3") (pinfunction "2_3") (pintype "passive"))
      (node (ref "U1") (pin "1") (pinfunction "PC6(/RESET)_1") (pintype "bidirectional"))
    )
    (net (code "48") (name "RST_3V3") (class "Default")
      (node (ref "U5") (pin "15") (pinfunction "6Y_15") (pintype "bidirectional"))
      (node (ref "U6") (pin "A14") (pinfunction "RST_A14") (pintype "bidirectional"))
      (node (ref "U6") (pin "A6") (pinfunction "RST_A6") (pintype "bidirectional"))
    )
    (net (code "49") (name "SCK_3V3") (class "Default")
      (node (ref "U5") (pin "4") (pinfunction "2Y_4") (pintype "bidirectional"))
      (node (ref "U6") (pin "A12") (pinfunction "SCK_A12") (pintype "bidirectional"))
      (node (ref "U6") (pin "A4") (pinfunction "SCK_A4") (pintype "bidirectional"))
    )
    (net (code "50") (name "SCL_3V3") (class "Default")
      (node (ref "Q5") (pin "2") (pinfunction "S_2") (pintype "bidirectional"))
      (node (ref "R11") (pin "1") (pinfunction "1_1") (pintype "passive"))
      (node (ref "U7") (pin "14") (pinfunction "SCL_14") (pintype "bidirectional"))
    )
    (net (code "51") (name "SDA_3V3") (class "Default")
      (node (ref "Q3") (pin "2") (pinfunction "S_2") (pintype "bidirectional"))
      (node (ref "R9") (pin "1") (pinfunction "1_1") (pintype "passive"))
      (node (ref "U7") (pin "13") (pinfunction "SDA_13") (pintype "bidirectional"))
    )
    (net (code "52") (name "USB_VCC") (class "Default")
      (node (ref "D3") (pin "A") (pinfunction "A_A") (pintype "passive"))
      (node (ref "F1") (pin "1") (pinfunction "1_1") (pintype "bidirectional"))
      (node (ref "R1") (pin "2") (pinfunction "2_2") (pintype "passive"))
      (node (ref "U2") (pin "16") (pinfunction "VCC_16") (pintype "bidirectional"))
    )
    (net (code "53") (name "VIN") (class "Default")
      (node (ref "C1") (pin "+") (pinfunction "+_+") (pintype "passive"))
      (node (ref "D1") (pin "C") (pinfunction "C_C") (pintype "passive"))
      (node (ref "JP1") (pin "VIN") (pinfunction "VIN_VIN") (pintype "power_in"))
      (node (ref "U3") (pin "3") (pinfunction "VIN_3") (pintype "input"))
    )
    (net (code "54") (name "unconnected-(J1-PadID1)") (class "Default")
      (node (ref "J1") (pin "ID1") (pinfunction "ID1_ID1") (pintype "bidirectional"))
    )
    (net (code "55") (name "unconnected-(JP1-PadRESERVED)") (class "Default")
      (node (ref "JP1") (pin "RESERVED") (pinfunction "RESERVED_RESERVED") (pintype "no_connect"))
    )
    (net (code "56") (name "unconnected-(U2-CTS-Pad9)") (class "Default")
      (node (ref "U2") (pin "9") (pinfunction "CTS_9") (pintype "bidirectional"))
    )
    (net (code "57") (name "unconnected-(U2-DCD-Pad12)") (class "Default")
      (node (ref "U2") (pin "12") (pinfunction "DCD_12") (pintype "bidirectional"))
    )
    (net (code "58") (name "unconnected-(U2-DSR-Pad10)") (class "Default")
      (node (ref "U2") (pin "10") (pinfunction "DSR_10") (pintype "bidirectional"))
    )
    (net (code "59") (name "unconnected-(U2-RI-Pad11)") (class "Default")
      (node (ref "U2") (pin "11") (pinfunction "RI_11") (pintype "bidirectional"))
    )
    (net (code "60") (name "unconnected-(U2-RS232-Pad15)") (class "Default")
      (node (ref "U2") (pin "15") (pinfunction "RS232_15") (pintype "bidirectional"))
    )
    (net (code "61") (name "unconnected-(U2-RTS-Pad14)") (class "Default")
      (node (ref "U2") (pin "14") (pinfunction "RTS_14") (pintype "bidirectional"))
    )
    (net (code "62") (name "unconnected-(U5-4A-Pad9)") (class "Default")
      (node (ref "U5") (pin "9") (pinfunction "4A_9") (pintype "bidirectional"))
    )
    (net (code "63") (name "unconnected-(U5-4Y-Pad10)") (class "Default")
      (node (ref "U5") (pin "10") (pinfunction "4Y_10") (pintype "bidirectional"))
    )
    (net (code "64") (name "unconnected-(U5-5A-Pad11)") (class "Default")
      (node (ref "U5") (pin "11") (pinfunction "5A_11") (pintype "bidirectional"))
    )
    (net (code "65") (name "unconnected-(U5-5Y-Pad12)") (class "Default")
      (node (ref "U5") (pin "12") (pinfunction "5Y_12") (pintype "bidirectional"))
    )
    (net (code "66") (name "unconnected-(U7-INT2-Pad9)") (class "Default")
      (node (ref "U7") (pin "9") (pinfunction "INT2_9") (pintype "bidirectional"))
    )
    (net (code "67") (name "unconnected-(U7-NC-Pad3)") (class "Default")
      (node (ref "U7") (pin "3") (pinfunction "NC_3") (pintype "bidirectional"))
    )
    (net (code "68") (name "unconnected-(U7-NC-Pad10)") (class "Default")
      (node (ref "U7") (pin "10") (pinfunction "NC_10") (pintype "bidirectional"))
    )
    (net (code "69") (name "unconnected-(U7-NC-Pad11)") (class "Default")
      (node (ref "U7") (pin "11") (pinfunction "NC_11") (pintype "bidirectional"))
    )
  )
)
